# SCH_2022-09-02.net
KiCad netlist of a schematic drawn in EasyEDA
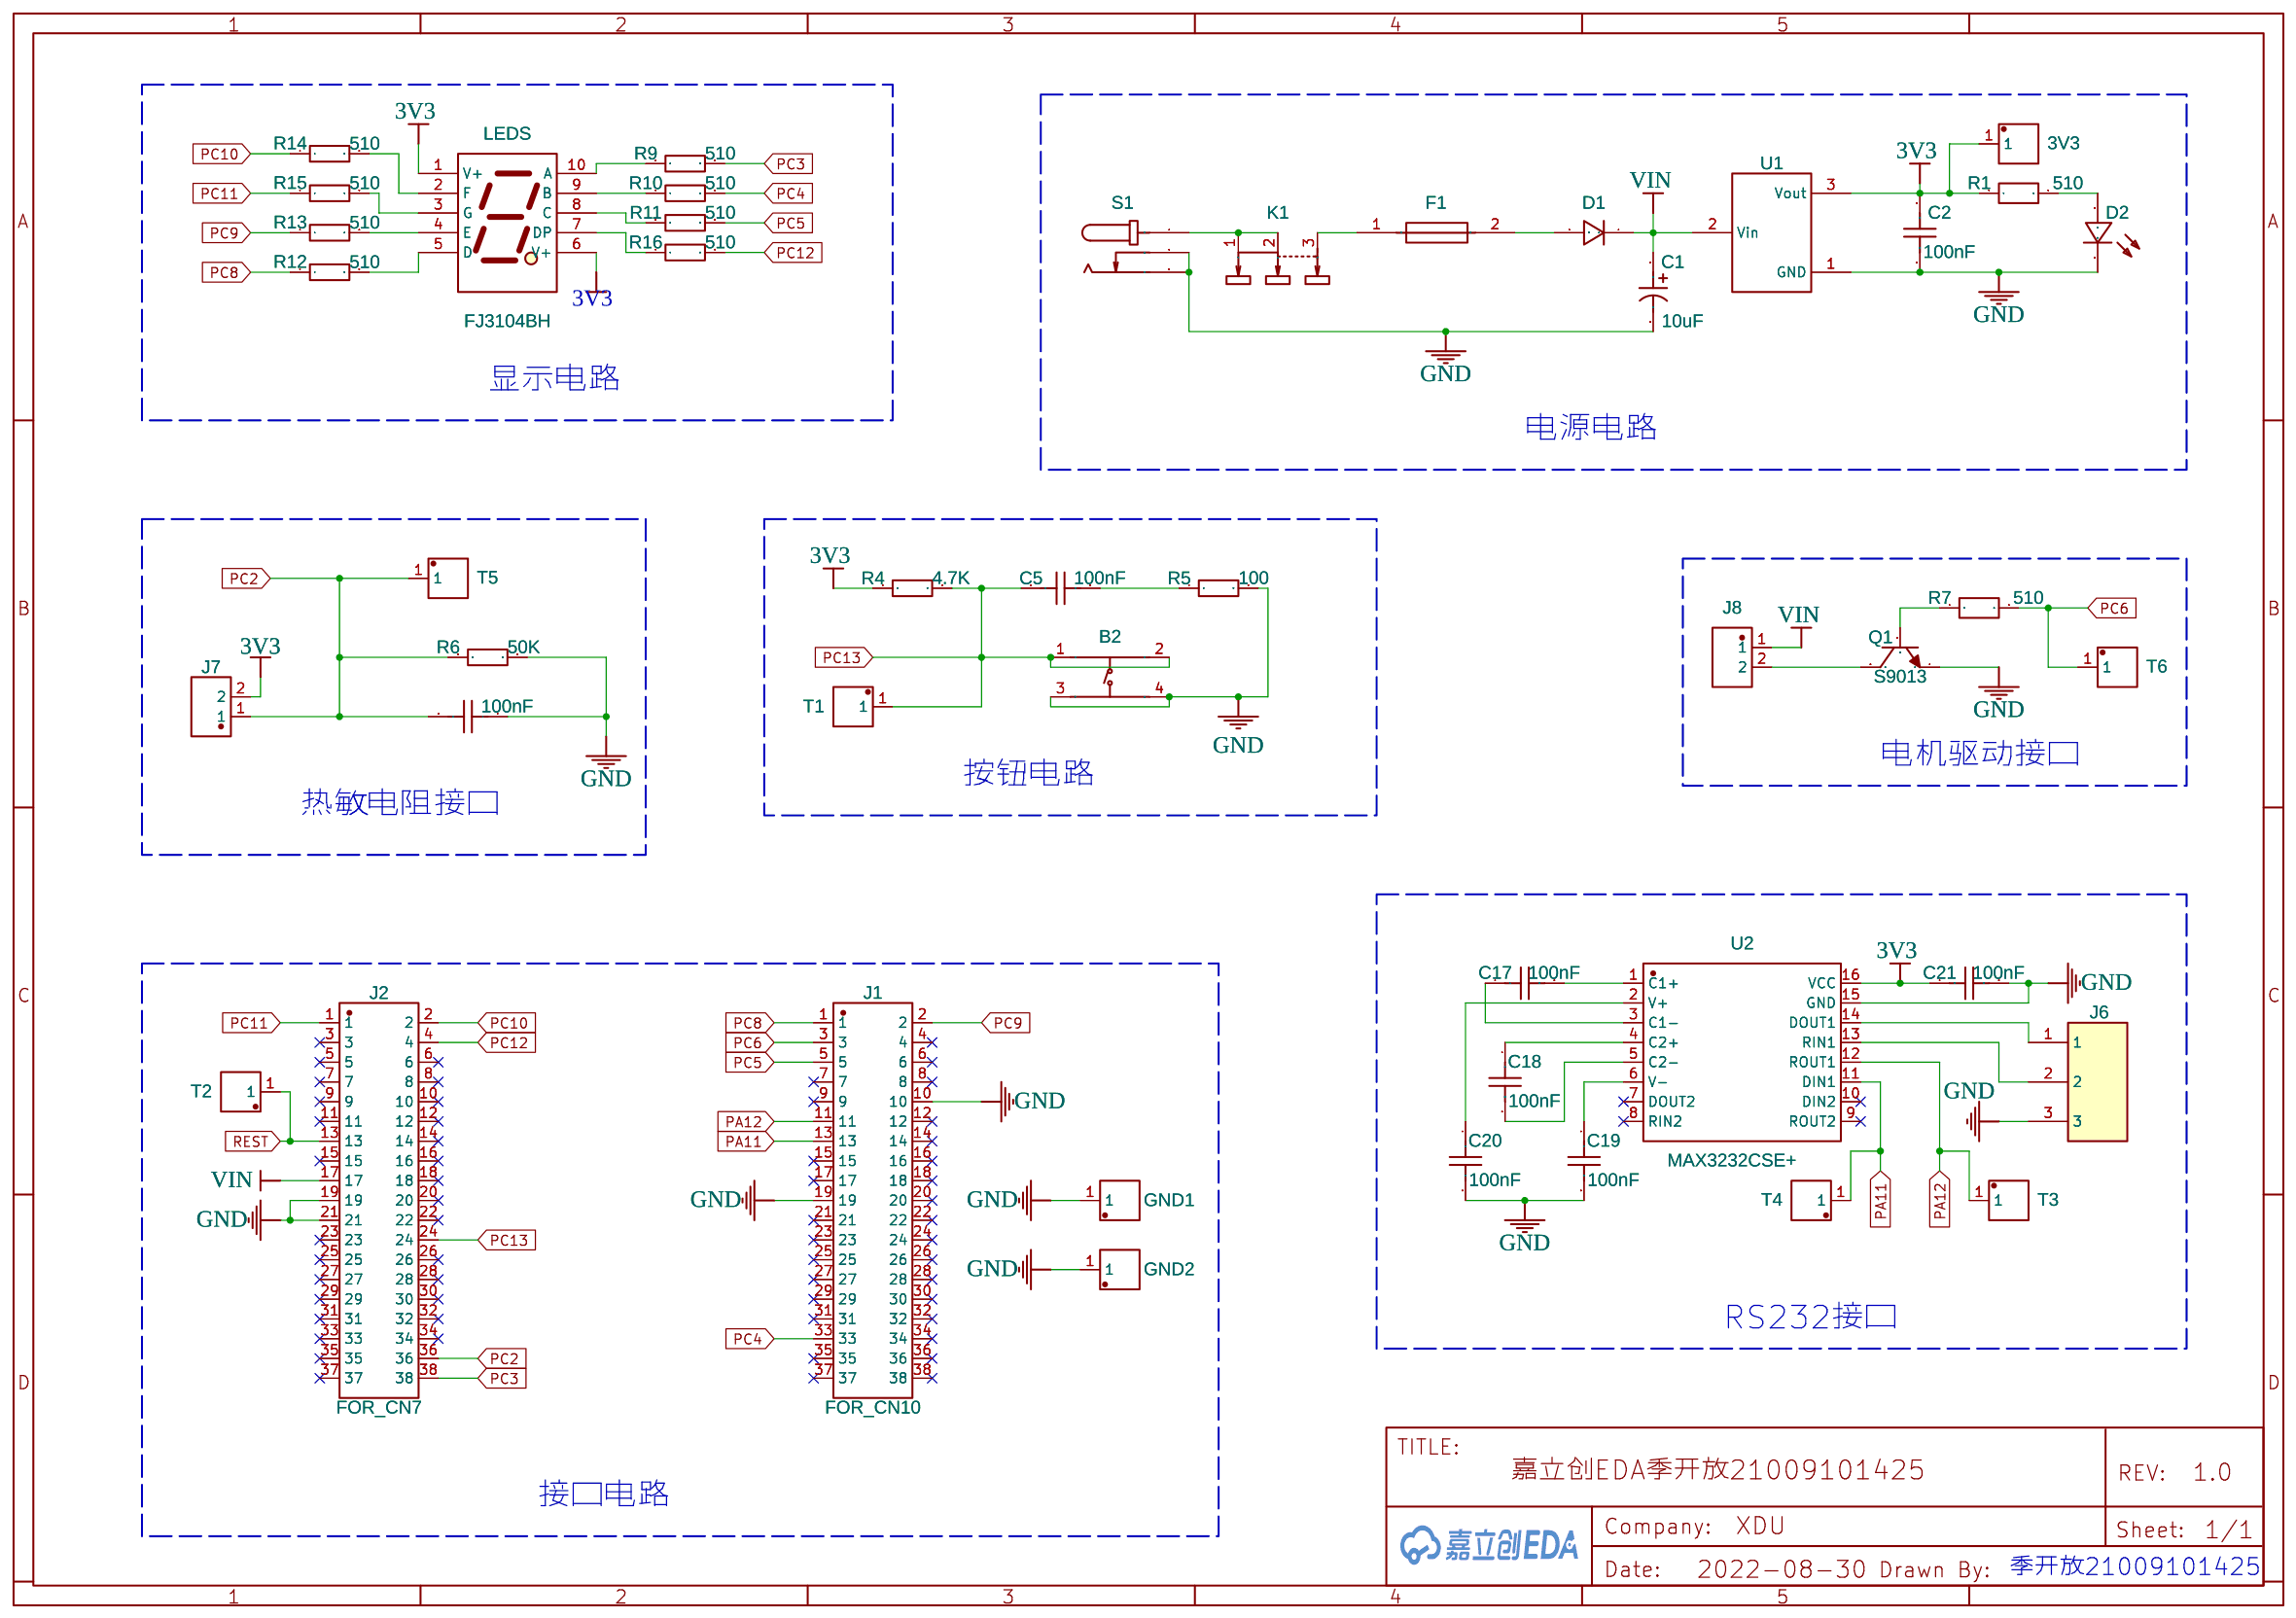
[diagram p0: schematic sheet]

(export (version "E")
  (design (tool "Eeschema 10.0.6"))
  (components
    (comp (ref "3V3")
      (value "54101-T06-00")
      (fields (field (name "BOM_Supplier Part") "C213463"))
      (libsource (lib "") (part "54101-T06-00_4"))
    )
    (comp (ref "B2")
      (value "TS665CJ")
      (fields (field (name "BOM_Supplier Part") "C393938"))
      (libsource (lib "") (part "TS665CJ"))
    )
    (comp (ref "C1")
      (value "10uF")
      (fields
        (field (name "BOM_Manufacturer Part") "50V10uF CD110")
        (field (name "BOM_Supplier Part") "C2960200")
      )
      (libsource (lib "") (part "50V10UF CD110"))
    )
    (comp (ref "C2")
      (value "100nF")
      (fields
        (field (name "BOM_Manufacturer Part") "CT4-0805B104K500F3")
        (field (name "BOM_Supplier Part") "C84772")
      )
      (libsource (lib "") (part "CT4-0805B104K500F3"))
    )
    (comp (ref "C3")
      (value "100nF")
      (fields
        (field (name "BOM_Manufacturer Part") "CT4-0805B104K500F3")
        (field (name "BOM_Supplier Part") "C84772")
      )
      (libsource (lib "") (part "CT4-0805B104K500F3_1"))
    )
    (comp (ref "C5")
      (value "100nF")
      (fields
        (field (name "BOM_Manufacturer Part") "CT4-0805B104K500F3")
        (field (name "BOM_Supplier Part") "C84772")
      )
      (libsource (lib "") (part "CT4-0805B104K500F3_1"))
    )
    (comp (ref "C17")
      (value "100nF")
      (fields
        (field (name "BOM_Manufacturer Part") "CT4-0805B104K500F3")
        (field (name "BOM_Supplier Part") "C84772")
      )
      (libsource (lib "") (part "CT4-0805B104K500F3_2"))
    )
    (comp (ref "C18")
      (value "100nF")
      (fields
        (field (name "BOM_Manufacturer Part") "CT4-0805B104K500F3")
        (field (name "BOM_Supplier Part") "C84772")
      )
      (libsource (lib "") (part "CT4-0805B104K500F3"))
    )
    (comp (ref "C19")
      (value "100nF")
      (fields
        (field (name "BOM_Manufacturer Part") "CT4-0805B104K500F3")
        (field (name "BOM_Supplier Part") "C84772")
      )
      (libsource (lib "") (part "CT4-0805B104K500F3"))
    )
    (comp (ref "C20")
      (value "100nF")
      (fields
        (field (name "BOM_Manufacturer Part") "CT4-0805B104K500F3")
        (field (name "BOM_Supplier Part") "C84772")
      )
      (libsource (lib "") (part "CT4-0805B104K500F3"))
    )
    (comp (ref "C21")
      (value "100nF")
      (fields
        (field (name "BOM_Manufacturer Part") "CT4-0805B104K500F3")
        (field (name "BOM_Supplier Part") "C84772")
      )
      (libsource (lib "") (part "CT4-0805B104K500F3_2"))
    )
    (comp (ref "D1")
      (value "1N5817_C169165")
      (fields (field (name "BOM_Manufacturer Part") "1N5817") (field (name "BOM_Supplier Part") "C169165"))
      (libsource (lib "") (part "1N5817_C169165"))
    )
    (comp (ref "D2")
      (value "TJ-L3FYTGHTFCLFLC2R-A5")
      (fields (field (name "BOM_Supplier Part") "C330746"))
      (libsource (lib "") (part "TJ-L3FYTGHTFCLFLC2R-A5"))
    )
    (comp (ref "F1")
      (value "A72-065")
      (fields (field (name "BOM_Supplier Part") "C135426"))
      (libsource (lib "") (part "A72-065"))
    )
    (comp (ref "GND1")
      (value "54101-T06-00")
      (fields (field (name "BOM_Supplier Part") "C213463"))
      (libsource (lib "") (part "54101-T06-00_3"))
    )
    (comp (ref "GND2")
      (value "54101-T06-00")
      (fields (field (name "BOM_Supplier Part") "C213463"))
      (libsource (lib "") (part "54101-T06-00_3"))
    )
    (comp (ref "J1")
      (value "FOR_CN10")
      (fields
        (field (name "BOM_Manufacturer Part") "PM254-2-19-Z-8.5")
        (field (name "BOM_Supplier Part") "C2897420")
      )
      (libsource (lib "") (part "PM254-2-19-Z-8.5"))
    )
    (comp (ref "J2")
      (value "FOR_CN7")
      (fields
        (field (name "BOM_Manufacturer Part") "PM254-2-19-Z-8.5")
        (field (name "BOM_Supplier Part") "C2897420")
      )
      (libsource (lib "") (part "PM254-2-19-Z-8.5"))
    )
    (comp (ref "J6")
      (value "WJ124-3.81-3P")
      (fields (field (name "BOM_Supplier Part") "C36780"))
      (libsource (lib "") (part "WJ124-3.81-3P"))
    )
    (comp (ref "J7")
      (value "WJ124-3.81-2P")
      (fields (field (name "BOM_Supplier Part") "C69811"))
      (libsource (lib "") (part "WJ124-3.81-2P_1"))
    )
    (comp (ref "J8")
      (value "WJ124-3.81-2P")
      (fields (field (name "BOM_Supplier Part") "C69811"))
      (libsource (lib "") (part "WJ124-3.81-2P"))
    )
    (comp (ref "K1")
      (value "SS-12D10L5")
      (fields (field (name "BOM_Supplier Part") "C319012"))
      (libsource (lib "") (part "SS-12D10L5"))
    )
    (comp (ref "LEDS")
      (value "FJ3104BH")
      (fields (field (name "BOM_Supplier Part") "C2938319"))
      (libsource (lib "") (part "FJ3104BH"))
    )
    (comp (ref "Q1")
      (value "S9013")
      (fields (field (name "BOM_Supplier Part") "C6748"))
      (libsource (lib "") (part "S9013"))
    )
    (comp (ref "R1")
      (value "510")
      (fields
        (field (name "BOM_Manufacturer Part") "MF1/8W-10KΩ±1%T52")
        (field (name "BOM_Supplier Part") "C713919")
      )
      (libsource (lib "") (part "MF1/8W-10KΩ±1%T52"))
    )
    (comp (ref "R4")
      (value "4.7K")
      (fields (field (name "BOM_Supplier Part") "C119149"))
      (libsource (lib "") (part "MF1/8W-43Ω±1% T52"))
    )
    (comp (ref "R5")
      (value "100")
      (fields (field (name "BOM_Supplier Part") "C119149"))
      (libsource (lib "") (part "MF1/8W-43Ω±1% T52"))
    )
    (comp (ref "R6")
      (value "50K")
      (fields (field (name "BOM_Supplier Part") "C119149"))
      (libsource (lib "") (part "MF1/8W-43Ω±1% T52"))
    )
    (comp (ref "R7")
      (value "510")
      (fields
        (field (name "BOM_Manufacturer Part") "MF1/8W-10KΩ±1%T52")
        (field (name "BOM_Supplier Part") "C713919")
      )
      (libsource (lib "") (part "MF1/8W-10KΩ±1%T52"))
    )
    (comp (ref "R9")
      (value "510")
      (fields (field (name "BOM_Supplier Part") "C119149"))
      (libsource (lib "") (part "MF1/8W-43Ω±1% T52"))
    )
    (comp (ref "R10")
      (value "510")
      (fields (field (name "BOM_Supplier Part") "C119149"))
      (libsource (lib "") (part "MF1/8W-43Ω±1% T52"))
    )
    (comp (ref "R11")
      (value "510")
      (fields (field (name "BOM_Supplier Part") "C119149"))
      (libsource (lib "") (part "MF1/8W-43Ω±1% T52"))
    )
    (comp (ref "R12")
      (value "510")
      (fields (field (name "BOM_Supplier Part") "C119149"))
      (libsource (lib "") (part "MF1/8W-43Ω±1% T52"))
    )
    (comp (ref "R13")
      (value "510")
      (fields (field (name "BOM_Supplier Part") "C119149"))
      (libsource (lib "") (part "MF1/8W-43Ω±1% T52"))
    )
    (comp (ref "R14")
      (value "510")
      (fields (field (name "BOM_Supplier Part") "C119149"))
      (libsource (lib "") (part "MF1/8W-43Ω±1% T52"))
    )
    (comp (ref "R15")
      (value "510")
      (fields (field (name "BOM_Supplier Part") "C119149"))
      (libsource (lib "") (part "MF1/8W-43Ω±1% T52"))
    )
    (comp (ref "R16")
      (value "510")
      (fields (field (name "BOM_Supplier Part") "C119149"))
      (libsource (lib "") (part "MF1/8W-43Ω±1% T52"))
    )
    (comp (ref "S1")
      (value "JPD1030-N521-4F")
      (fields (field (name "BOM_Supplier Part") "C426213"))
      (libsource (lib "") (part "JPD1030-N521-4F"))
    )
    (comp (ref "T1")
      (value "54101-T06-00")
      (fields (field (name "BOM_Supplier Part") "C213463"))
      (libsource (lib "") (part "54101-T06-00_2"))
    )
    (comp (ref "T2")
      (value "54101-T06-00")
      (fields (field (name "BOM_Supplier Part") "C213463"))
      (libsource (lib "") (part "54101-T06-00"))
    )
    (comp (ref "T3")
      (value "54101-T06-00")
      (fields (field (name "BOM_Supplier Part") "C213463"))
      (libsource (lib "") (part "54101-T06-00_1"))
    )
    (comp (ref "T4")
      (value "54101-T06-00")
      (fields (field (name "BOM_Supplier Part") "C213463"))
      (libsource (lib "") (part "54101-T06-00"))
    )
    (comp (ref "T5")
      (value "54101-T06-00")
      (fields (field (name "BOM_Supplier Part") "C213463"))
      (libsource (lib "") (part "54101-T06-00_1"))
    )
    (comp (ref "T6")
      (value "54101-T06-00")
      (fields (field (name "BOM_Supplier Part") "C213463"))
      (libsource (lib "") (part "54101-T06-00_1"))
    )
    (comp (ref "U1")
      (value "HT7533-1_C32617")
      (fields (field (name "BOM_Manufacturer Part") "HT7533-1") (field (name "BOM_Supplier Part") "C32617"))
      (libsource (lib "") (part "HT7533-1_C32617"))
    )
    (comp (ref "U2")
      (value "MAX3232CSE+")
      (fields (field (name "BOM_Supplier Part") "C143430"))
      (libsource (lib "") (part "MAX3232CSE+"))
    )
  )
  (nets
    (net (code "1") (name "3V3") (class "Default")
      (node (ref "3V3") (pin "1") (pinfunction "1_1") (pintype "unspecified"))
      (node (ref "C2") (pin "1") (pinfunction "1_1") (pintype "unspecified"))
      (node (ref "C21") (pin "1") (pinfunction "1_1") (pintype "unspecified"))
      (node (ref "J7") (pin "2") (pinfunction "2_2") (pintype "unspecified"))
      (node (ref "LEDS") (pin "1") (pinfunction "V+_1") (pintype "unspecified"))
      (node (ref "LEDS") (pin "6") (pinfunction "V+_6") (pintype "unspecified"))
      (node (ref "R1") (pin "1") (pinfunction "1_1") (pintype "unspecified"))
      (node (ref "R4") (pin "1") (pinfunction "1_1") (pintype "unspecified"))
      (node (ref "U1") (pin "3") (pinfunction "Vout_3") (pintype "unspecified"))
      (node (ref "U2") (pin "16") (pinfunction "VCC_16") (pintype "unspecified"))
    )
    (net (code "2") (name "GND") (class "Default")
      (node (ref "B2") (pin "3") (pinfunction "C_3") (pintype "unspecified"))
      (node (ref "B2") (pin "4") (pinfunction "D_4") (pintype "unspecified"))
      (node (ref "C1") (pin "2") (pinfunction "2_2") (pintype "input"))
      (node (ref "C19") (pin "2") (pinfunction "2_2") (pintype "unspecified"))
      (node (ref "C2") (pin "2") (pinfunction "2_2") (pintype "unspecified"))
      (node (ref "C20") (pin "2") (pinfunction "2_2") (pintype "unspecified"))
      (node (ref "C21") (pin "2") (pinfunction "2_2") (pintype "unspecified"))
      (node (ref "C3") (pin "1") (pinfunction "1_1") (pintype "unspecified"))
      (node (ref "D2") (pin "2") (pinfunction "2_2") (pintype "unspecified"))
      (node (ref "GND1") (pin "1") (pinfunction "1_1") (pintype "unspecified"))
      (node (ref "GND2") (pin "1") (pinfunction "1_1") (pintype "unspecified"))
      (node (ref "J1") (pin "10") (pinfunction "10_10") (pintype "unspecified"))
      (node (ref "J1") (pin "19") (pinfunction "19_19") (pintype "unspecified"))
      (node (ref "J2") (pin "19") (pinfunction "19_19") (pintype "unspecified"))
      (node (ref "J2") (pin "21") (pinfunction "21_21") (pintype "unspecified"))
      (node (ref "J6") (pin "3") (pinfunction "3_3") (pintype "input"))
      (node (ref "Q1") (pin "1") (pinfunction "E_1") (pintype "unspecified"))
      (node (ref "R5") (pin "2") (pinfunction "2_2") (pintype "unspecified"))
      (node (ref "R6") (pin "2") (pinfunction "2_2") (pintype "unspecified"))
      (node (ref "S1") (pin "2") (pinfunction "2_2") (pintype "unspecified"))
      (node (ref "S1") (pin "3") (pinfunction "3_3") (pintype "unspecified"))
      (node (ref "U1") (pin "1") (pinfunction "GND_1") (pintype "unspecified"))
      (node (ref "U2") (pin "15") (pinfunction "GND_15") (pintype "unspecified"))
    )
    (net (code "3") (name "Net-(C5-Pad1)") (class "Default")
      (node (ref "C5") (pin "1") (pinfunction "1_1") (pintype "unspecified"))
      (node (ref "R5") (pin "1") (pinfunction "1_1") (pintype "unspecified"))
    )
    (net (code "4") (name "Net-(D1-Pad2)") (class "Default")
      (node (ref "D1") (pin "2") (pinfunction "2_2") (pintype "unspecified"))
      (node (ref "F1") (pin "2") (pinfunction "2_2") (pintype "unspecified"))
    )
    (net (code "5") (name "Net-(D2-Pad1)") (class "Default")
      (node (ref "D2") (pin "1") (pinfunction "1_1") (pintype "unspecified"))
      (node (ref "R1") (pin "2") (pinfunction "2_2") (pintype "unspecified"))
    )
    (net (code "6") (name "Net-(F1-Pad1)") (class "Default")
      (node (ref "F1") (pin "1") (pinfunction "1_1") (pintype "unspecified"))
      (node (ref "K1") (pin "3") (pinfunction "3_3") (pintype "unspecified"))
    )
    (net (code "7") (name "Net-(K1-Pad1)") (class "Default")
      (node (ref "K1") (pin "1") (pinfunction "1_1") (pintype "unspecified"))
      (node (ref "K1") (pin "2") (pinfunction "2_2") (pintype "unspecified"))
      (node (ref "S1") (pin "1") (pinfunction "1_1") (pintype "unspecified"))
    )
    (net (code "8") (name "Net-(LEDS-A)") (class "Default")
      (node (ref "LEDS") (pin "10") (pinfunction "A_10") (pintype "unspecified"))
      (node (ref "R9") (pin "1") (pinfunction "1_1") (pintype "unspecified"))
    )
    (net (code "9") (name "Net-(LEDS-B)") (class "Default")
      (node (ref "LEDS") (pin "9") (pinfunction "B_9") (pintype "unspecified"))
      (node (ref "R10") (pin "1") (pinfunction "1_1") (pintype "unspecified"))
    )
    (net (code "10") (name "Net-(LEDS-C)") (class "Default")
      (node (ref "LEDS") (pin "8") (pinfunction "C_8") (pintype "unspecified"))
      (node (ref "R11") (pin "1") (pinfunction "1_1") (pintype "unspecified"))
    )
    (net (code "11") (name "Net-(LEDS-D)") (class "Default")
      (node (ref "LEDS") (pin "5") (pinfunction "D_5") (pintype "unspecified"))
      (node (ref "R12") (pin "2") (pinfunction "2_2") (pintype "unspecified"))
    )
    (net (code "12") (name "Net-(LEDS-DP)") (class "Default")
      (node (ref "LEDS") (pin "7") (pinfunction "DP_7") (pintype "unspecified"))
      (node (ref "R16") (pin "1") (pinfunction "1_1") (pintype "unspecified"))
    )
    (net (code "13") (name "Net-(LEDS-E)") (class "Default")
      (node (ref "LEDS") (pin "4") (pinfunction "E_4") (pintype "unspecified"))
      (node (ref "R13") (pin "2") (pinfunction "2_2") (pintype "unspecified"))
    )
    (net (code "14") (name "Net-(LEDS-F)") (class "Default")
      (node (ref "LEDS") (pin "2") (pinfunction "F_2") (pintype "unspecified"))
      (node (ref "R14") (pin "2") (pinfunction "2_2") (pintype "unspecified"))
    )
    (net (code "15") (name "Net-(LEDS-G)") (class "Default")
      (node (ref "LEDS") (pin "3") (pinfunction "G_3") (pintype "unspecified"))
      (node (ref "R15") (pin "2") (pinfunction "2_2") (pintype "unspecified"))
    )
    (net (code "16") (name "Net-(Q1-B)") (class "Default")
      (node (ref "Q1") (pin "2") (pinfunction "B_2") (pintype "unspecified"))
      (node (ref "R7") (pin "1") (pinfunction "1_1") (pintype "unspecified"))
    )
    (net (code "17") (name "Net-(Q1-C)") (class "Default")
      (node (ref "J8") (pin "2") (pinfunction "2_2") (pintype "unspecified"))
      (node (ref "Q1") (pin "3") (pinfunction "C_3") (pintype "unspecified"))
    )
    (net (code "18") (name "Net-(U2-C1+)") (class "Default")
      (node (ref "C17") (pin "2") (pinfunction "2_2") (pintype "unspecified"))
      (node (ref "U2") (pin "1") (pinfunction "C1+_1") (pintype "unspecified"))
    )
    (net (code "19") (name "Net-(U2-C1-)") (class "Default")
      (node (ref "C17") (pin "1") (pinfunction "1_1") (pintype "unspecified"))
      (node (ref "U2") (pin "3") (pinfunction "C1-_3") (pintype "unspecified"))
    )
    (net (code "20") (name "Net-(U2-C2+)") (class "Default")
      (node (ref "C18") (pin "1") (pinfunction "1_1") (pintype "unspecified"))
      (node (ref "U2") (pin "4") (pinfunction "C2+_4") (pintype "unspecified"))
    )
    (net (code "21") (name "Net-(U2-C2-)") (class "Default")
      (node (ref "C18") (pin "2") (pinfunction "2_2") (pintype "unspecified"))
      (node (ref "U2") (pin "5") (pinfunction "C2-_5") (pintype "unspecified"))
    )
    (net (code "22") (name "Net-(U2-DOUT1)") (class "Default")
      (node (ref "J6") (pin "1") (pinfunction "1_1") (pintype "input"))
      (node (ref "U2") (pin "14") (pinfunction "DOUT1_14") (pintype "unspecified"))
    )
    (net (code "23") (name "Net-(U2-RIN1)") (class "Default")
      (node (ref "J6") (pin "2") (pinfunction "2_2") (pintype "input"))
      (node (ref "U2") (pin "13") (pinfunction "RIN1_13") (pintype "unspecified"))
    )
    (net (code "24") (name "Net-(U2-V+)") (class "Default")
      (node (ref "C20") (pin "1") (pinfunction "1_1") (pintype "unspecified"))
      (node (ref "U2") (pin "2") (pinfunction "V+_2") (pintype "unspecified"))
    )
    (net (code "25") (name "Net-(U2-V-)") (class "Default")
      (node (ref "C19") (pin "1") (pinfunction "1_1") (pintype "unspecified"))
      (node (ref "U2") (pin "6") (pinfunction "V-_6") (pintype "unspecified"))
    )
    (net (code "26") (name "PA11") (class "Default")
      (node (ref "J1") (pin "13") (pinfunction "13_13") (pintype "unspecified"))
      (node (ref "T4") (pin "1") (pinfunction "1_1") (pintype "unspecified"))
      (node (ref "U2") (pin "11") (pinfunction "DIN1_11") (pintype "unspecified"))
    )
    (net (code "27") (name "PA12") (class "Default")
      (node (ref "J1") (pin "11") (pinfunction "11_11") (pintype "unspecified"))
      (node (ref "T3") (pin "1") (pinfunction "1_1") (pintype "unspecified"))
      (node (ref "U2") (pin "12") (pinfunction "ROUT1_12") (pintype "unspecified"))
    )
    (net (code "28") (name "PC2") (class "Default")
      (node (ref "C3") (pin "2") (pinfunction "2_2") (pintype "unspecified"))
      (node (ref "J2") (pin "36") (pinfunction "36_36") (pintype "unspecified"))
      (node (ref "J7") (pin "1") (pinfunction "1_1") (pintype "unspecified"))
      (node (ref "R6") (pin "1") (pinfunction "1_1") (pintype "unspecified"))
      (node (ref "T5") (pin "1") (pinfunction "1_1") (pintype "unspecified"))
    )
    (net (code "29") (name "PC3") (class "Default")
      (node (ref "J2") (pin "38") (pinfunction "38_38") (pintype "unspecified"))
      (node (ref "R9") (pin "2") (pinfunction "2_2") (pintype "unspecified"))
    )
    (net (code "30") (name "PC4") (class "Default")
      (node (ref "J1") (pin "33") (pinfunction "33_33") (pintype "unspecified"))
      (node (ref "R10") (pin "2") (pinfunction "2_2") (pintype "unspecified"))
    )
    (net (code "31") (name "PC5") (class "Default")
      (node (ref "J1") (pin "5") (pinfunction "5_5") (pintype "unspecified"))
      (node (ref "R11") (pin "2") (pinfunction "2_2") (pintype "unspecified"))
    )
    (net (code "32") (name "PC6") (class "Default")
      (node (ref "J1") (pin "3") (pinfunction "3_3") (pintype "unspecified"))
      (node (ref "R7") (pin "2") (pinfunction "2_2") (pintype "unspecified"))
      (node (ref "T6") (pin "1") (pinfunction "1_1") (pintype "unspecified"))
    )
    (net (code "33") (name "PC8") (class "Default")
      (node (ref "J1") (pin "1") (pinfunction "1_1") (pintype "unspecified"))
      (node (ref "R12") (pin "1") (pinfunction "1_1") (pintype "unspecified"))
    )
    (net (code "34") (name "PC9") (class "Default")
      (node (ref "J1") (pin "2") (pinfunction "2_2") (pintype "unspecified"))
      (node (ref "R13") (pin "1") (pinfunction "1_1") (pintype "unspecified"))
    )
    (net (code "35") (name "PC10") (class "Default")
      (node (ref "J2") (pin "2") (pinfunction "2_2") (pintype "unspecified"))
      (node (ref "R14") (pin "1") (pinfunction "1_1") (pintype "unspecified"))
    )
    (net (code "36") (name "PC11") (class "Default")
      (node (ref "J2") (pin "1") (pinfunction "1_1") (pintype "unspecified"))
      (node (ref "R15") (pin "1") (pinfunction "1_1") (pintype "unspecified"))
    )
    (net (code "37") (name "PC12") (class "Default")
      (node (ref "J2") (pin "4") (pinfunction "4_4") (pintype "unspecified"))
      (node (ref "R16") (pin "2") (pinfunction "2_2") (pintype "unspecified"))
    )
    (net (code "38") (name "PC13") (class "Default")
      (node (ref "B2") (pin "1") (pinfunction "A_1") (pintype "unspecified"))
      (node (ref "B2") (pin "2") (pinfunction "B_2") (pintype "unspecified"))
      (node (ref "C5") (pin "2") (pinfunction "2_2") (pintype "unspecified"))
      (node (ref "J2") (pin "24") (pinfunction "24_24") (pintype "unspecified"))
      (node (ref "R4") (pin "2") (pinfunction "2_2") (pintype "unspecified"))
      (node (ref "T1") (pin "1") (pinfunction "1_1") (pintype "unspecified"))
    )
    (net (code "39") (name "REST") (class "Default")
      (node (ref "J2") (pin "13") (pinfunction "13_13") (pintype "unspecified"))
      (node (ref "T2") (pin "1") (pinfunction "1_1") (pintype "unspecified"))
    )
    (net (code "40") (name "VIN") (class "Default")
      (node (ref "C1") (pin "1") (pinfunction "1_1") (pintype "input"))
      (node (ref "D1") (pin "1") (pinfunction "1_1") (pintype "unspecified"))
      (node (ref "J2") (pin "17") (pinfunction "17_17") (pintype "unspecified"))
      (node (ref "J8") (pin "1") (pinfunction "1_1") (pintype "unspecified"))
      (node (ref "U1") (pin "2") (pinfunction "Vin_2") (pintype "unspecified"))
    )
    (net (code "41") (name "unconnected-(J1-Pad4)") (class "Default")
      (node (ref "J1") (pin "4") (pinfunction "4_4") (pintype "unspecified+no_connect"))
    )
    (net (code "42") (name "unconnected-(J1-Pad6)") (class "Default")
      (node (ref "J1") (pin "6") (pinfunction "6_6") (pintype "unspecified+no_connect"))
    )
    (net (code "43") (name "unconnected-(J1-Pad7)") (class "Default")
      (node (ref "J1") (pin "7") (pinfunction "7_7") (pintype "unspecified+no_connect"))
    )
    (net (code "44") (name "unconnected-(J1-Pad8)") (class "Default")
      (node (ref "J1") (pin "8") (pinfunction "8_8") (pintype "unspecified+no_connect"))
    )
    (net (code "45") (name "unconnected-(J1-Pad9)") (class "Default")
      (node (ref "J1") (pin "9") (pinfunction "9_9") (pintype "unspecified+no_connect"))
    )
    (net (code "46") (name "unconnected-(J1-Pad12)") (class "Default")
      (node (ref "J1") (pin "12") (pinfunction "12_12") (pintype "unspecified+no_connect"))
    )
    (net (code "47") (name "unconnected-(J1-Pad14)") (class "Default")
      (node (ref "J1") (pin "14") (pinfunction "14_14") (pintype "unspecified+no_connect"))
    )
    (net (code "48") (name "unconnected-(J1-Pad15)") (class "Default")
      (node (ref "J1") (pin "15") (pinfunction "15_15") (pintype "unspecified+no_connect"))
    )
    (net (code "49") (name "unconnected-(J1-Pad16)") (class "Default")
      (node (ref "J1") (pin "16") (pinfunction "16_16") (pintype "unspecified+no_connect"))
    )
    (net (code "50") (name "unconnected-(J1-Pad17)") (class "Default")
      (node (ref "J1") (pin "17") (pinfunction "17_17") (pintype "unspecified+no_connect"))
    )
    (net (code "51") (name "unconnected-(J1-Pad18)") (class "Default")
      (node (ref "J1") (pin "18") (pinfunction "18_18") (pintype "unspecified+no_connect"))
    )
    (net (code "52") (name "unconnected-(J1-Pad20)") (class "Default")
      (node (ref "J1") (pin "20") (pinfunction "20_20") (pintype "unspecified+no_connect"))
    )
    (net (code "53") (name "unconnected-(J1-Pad21)") (class "Default")
      (node (ref "J1") (pin "21") (pinfunction "21_21") (pintype "unspecified+no_connect"))
    )
    (net (code "54") (name "unconnected-(J1-Pad22)") (class "Default")
      (node (ref "J1") (pin "22") (pinfunction "22_22") (pintype "unspecified+no_connect"))
    )
    (net (code "55") (name "unconnected-(J1-Pad23)") (class "Default")
      (node (ref "J1") (pin "23") (pinfunction "23_23") (pintype "unspecified+no_connect"))
    )
    (net (code "56") (name "unconnected-(J1-Pad24)") (class "Default")
      (node (ref "J1") (pin "24") (pinfunction "24_24") (pintype "unspecified+no_connect"))
    )
    (net (code "57") (name "unconnected-(J1-Pad25)") (class "Default")
      (node (ref "J1") (pin "25") (pinfunction "25_25") (pintype "unspecified+no_connect"))
    )
    (net (code "58") (name "unconnected-(J1-Pad26)") (class "Default")
      (node (ref "J1") (pin "26") (pinfunction "26_26") (pintype "unspecified+no_connect"))
    )
    (net (code "59") (name "unconnected-(J1-Pad27)") (class "Default")
      (node (ref "J1") (pin "27") (pinfunction "27_27") (pintype "unspecified+no_connect"))
    )
    (net (code "60") (name "unconnected-(J1-Pad28)") (class "Default")
      (node (ref "J1") (pin "28") (pinfunction "28_28") (pintype "unspecified+no_connect"))
    )
    (net (code "61") (name "unconnected-(J1-Pad29)") (class "Default")
      (node (ref "J1") (pin "29") (pinfunction "29_29") (pintype "unspecified+no_connect"))
    )
    (net (code "62") (name "unconnected-(J1-Pad30)") (class "Default")
      (node (ref "J1") (pin "30") (pinfunction "30_30") (pintype "unspecified+no_connect"))
    )
    (net (code "63") (name "unconnected-(J1-Pad31)") (class "Default")
      (node (ref "J1") (pin "31") (pinfunction "31_31") (pintype "unspecified+no_connect"))
    )
    (net (code "64") (name "unconnected-(J1-Pad32)") (class "Default")
      (node (ref "J1") (pin "32") (pinfunction "32_32") (pintype "unspecified+no_connect"))
    )
    (net (code "65") (name "unconnected-(J1-Pad34)") (class "Default")
      (node (ref "J1") (pin "34") (pinfunction "34_34") (pintype "unspecified+no_connect"))
    )
    (net (code "66") (name "unconnected-(J1-Pad35)") (class "Default")
      (node (ref "J1") (pin "35") (pinfunction "35_35") (pintype "unspecified+no_connect"))
    )
    (net (code "67") (name "unconnected-(J1-Pad36)") (class "Default")
      (node (ref "J1") (pin "36") (pinfunction "36_36") (pintype "unspecified+no_connect"))
    )
    (net (code "68") (name "unconnected-(J1-Pad37)") (class "Default")
      (node (ref "J1") (pin "37") (pinfunction "37_37") (pintype "unspecified+no_connect"))
    )
    (net (code "69") (name "unconnected-(J1-Pad38)") (class "Default")
      (node (ref "J1") (pin "38") (pinfunction "38_38") (pintype "unspecified+no_connect"))
    )
    (net (code "70") (name "unconnected-(J2-Pad3)") (class "Default")
      (node (ref "J2") (pin "3") (pinfunction "3_3") (pintype "unspecified+no_connect"))
    )
    (net (code "71") (name "unconnected-(J2-Pad5)") (class "Default")
      (node (ref "J2") (pin "5") (pinfunction "5_5") (pintype "unspecified+no_connect"))
    )
    (net (code "72") (name "unconnected-(J2-Pad6)") (class "Default")
      (node (ref "J2") (pin "6") (pinfunction "6_6") (pintype "unspecified+no_connect"))
    )
    (net (code "73") (name "unconnected-(J2-Pad7)") (class "Default")
      (node (ref "J2") (pin "7") (pinfunction "7_7") (pintype "unspecified+no_connect"))
    )
    (net (code "74") (name "unconnected-(J2-Pad8)") (class "Default")
      (node (ref "J2") (pin "8") (pinfunction "8_8") (pintype "unspecified+no_connect"))
    )
    (net (code "75") (name "unconnected-(J2-Pad9)") (class "Default")
      (node (ref "J2") (pin "9") (pinfunction "9_9") (pintype "unspecified+no_connect"))
    )
    (net (code "76") (name "unconnected-(J2-Pad10)") (class "Default")
      (node (ref "J2") (pin "10") (pinfunction "10_10") (pintype "unspecified+no_connect"))
    )
    (net (code "77") (name "unconnected-(J2-Pad11)") (class "Default")
      (node (ref "J2") (pin "11") (pinfunction "11_11") (pintype "unspecified+no_connect"))
    )
    (net (code "78") (name "unconnected-(J2-Pad12)") (class "Default")
      (node (ref "J2") (pin "12") (pinfunction "12_12") (pintype "unspecified+no_connect"))
    )
    (net (code "79") (name "unconnected-(J2-Pad14)") (class "Default")
      (node (ref "J2") (pin "14") (pinfunction "14_14") (pintype "unspecified+no_connect"))
    )
    (net (code "80") (name "unconnected-(J2-Pad15)") (class "Default")
      (node (ref "J2") (pin "15") (pinfunction "15_15") (pintype "unspecified+no_connect"))
    )
    (net (code "81") (name "unconnected-(J2-Pad16)") (class "Default")
      (node (ref "J2") (pin "16") (pinfunction "16_16") (pintype "unspecified+no_connect"))
    )
    (net (code "82") (name "unconnected-(J2-Pad18)") (class "Default")
      (node (ref "J2") (pin "18") (pinfunction "18_18") (pintype "unspecified+no_connect"))
    )
    (net (code "83") (name "unconnected-(J2-Pad20)") (class "Default")
      (node (ref "J2") (pin "20") (pinfunction "20_20") (pintype "unspecified+no_connect"))
    )
    (net (code "84") (name "unconnected-(J2-Pad22)") (class "Default")
      (node (ref "J2") (pin "22") (pinfunction "22_22") (pintype "unspecified+no_connect"))
    )
    (net (code "85") (name "unconnected-(J2-Pad23)") (class "Default")
      (node (ref "J2") (pin "23") (pinfunction "23_23") (pintype "unspecified+no_connect"))
    )
    (net (code "86") (name "unconnected-(J2-Pad25)") (class "Default")
      (node (ref "J2") (pin "25") (pinfunction "25_25") (pintype "unspecified+no_connect"))
    )
    (net (code "87") (name "unconnected-(J2-Pad26)") (class "Default")
      (node (ref "J2") (pin "26") (pinfunction "26_26") (pintype "unspecified+no_connect"))
    )
    (net (code "88") (name "unconnected-(J2-Pad27)") (class "Default")
      (node (ref "J2") (pin "27") (pinfunction "27_27") (pintype "unspecified+no_connect"))
    )
    (net (code "89") (name "unconnected-(J2-Pad28)") (class "Default")
      (node (ref "J2") (pin "28") (pinfunction "28_28") (pintype "unspecified+no_connect"))
    )
    (net (code "90") (name "unconnected-(J2-Pad29)") (class "Default")
      (node (ref "J2") (pin "29") (pinfunction "29_29") (pintype "unspecified+no_connect"))
    )
    (net (code "91") (name "unconnected-(J2-Pad30)") (class "Default")
      (node (ref "J2") (pin "30") (pinfunction "30_30") (pintype "unspecified+no_connect"))
    )
    (net (code "92") (name "unconnected-(J2-Pad31)") (class "Default")
      (node (ref "J2") (pin "31") (pinfunction "31_31") (pintype "unspecified+no_connect"))
    )
    (net (code "93") (name "unconnected-(J2-Pad32)") (class "Default")
      (node (ref "J2") (pin "32") (pinfunction "32_32") (pintype "unspecified+no_connect"))
    )
    (net (code "94") (name "unconnected-(J2-Pad33)") (class "Default")
      (node (ref "J2") (pin "33") (pinfunction "33_33") (pintype "unspecified+no_connect"))
    )
    (net (code "95") (name "unconnected-(J2-Pad34)") (class "Default")
      (node (ref "J2") (pin "34") (pinfunction "34_34") (pintype "unspecified+no_connect"))
    )
    (net (code "96") (name "unconnected-(J2-Pad35)") (class "Default")
      (node (ref "J2") (pin "35") (pinfunction "35_35") (pintype "unspecified+no_connect"))
    )
    (net (code "97") (name "unconnected-(J2-Pad37)") (class "Default")
      (node (ref "J2") (pin "37") (pinfunction "37_37") (pintype "unspecified+no_connect"))
    )
    (net (code "98") (name "unconnected-(U2-DIN2-Pad10)") (class "Default")
      (node (ref "U2") (pin "10") (pinfunction "DIN2_10") (pintype "unspecified+no_connect"))
    )
    (net (code "99") (name "unconnected-(U2-DOUT2-Pad7)") (class "Default")
      (node (ref "U2") (pin "7") (pinfunction "DOUT2_7") (pintype "unspecified+no_connect"))
    )
    (net (code "100") (name "unconnected-(U2-RIN2-Pad8)") (class "Default")
      (node (ref "U2") (pin "8") (pinfunction "RIN2_8") (pintype "unspecified+no_connect"))
    )
    (net (code "101") (name "unconnected-(U2-ROUT2-Pad9)") (class "Default")
      (node (ref "U2") (pin "9") (pinfunction "ROUT2_9") (pintype "unspecified+no_connect"))
    )
  )
)
